# K10_reg_proto.net
KiCad netlist of a schematic drawn in EAGLE
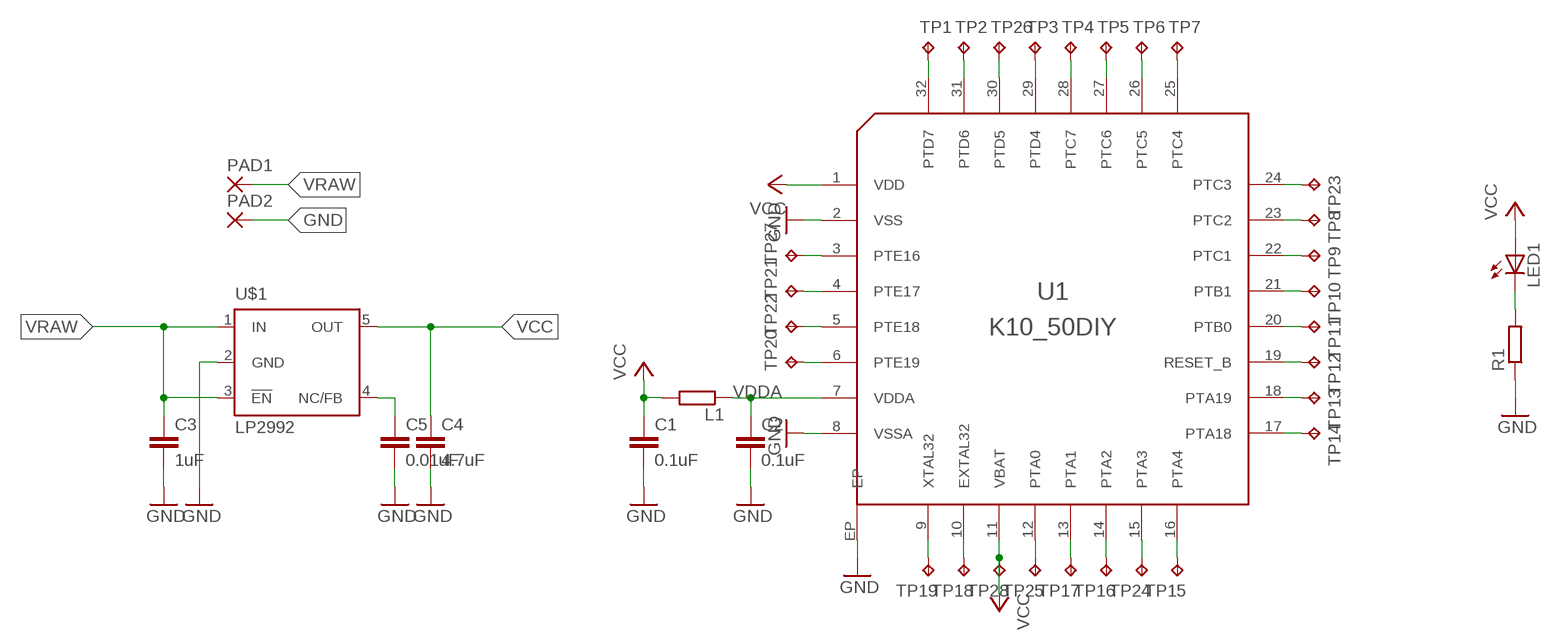
[diagram p0: schematic, sheet 1]

(export (version "E")
  (design (tool "Eeschema 10.0.6"))
  (components
    (comp (ref "C1")
      (value "0.1uF")
      (footprint "eagle-import:C0805")
      (libsource (lib "eagle-import") (part "C-EUC0805"))
    )
    (comp (ref "C2")
      (value "0.1uF")
      (footprint "eagle-import:C0805")
      (libsource (lib "eagle-import") (part "C-EUC0805"))
    )
    (comp (ref "C3")
      (value "1uF")
      (footprint "eagle-import:C0805")
      (libsource (lib "eagle-import") (part "C-EUC0805"))
    )
    (comp (ref "C4")
      (value "4.7uF")
      (footprint "eagle-import:C0805")
      (libsource (lib "eagle-import") (part "C-EUC0805"))
    )
    (comp (ref "C5")
      (value "0.01uF")
      (footprint "eagle-import:C0805")
      (libsource (lib "eagle-import") (part "C-EUC0805"))
    )
    (comp (ref "L1")
      (value "R-EU_R1206")
      (footprint "eagle-import:R1206")
      (libsource (lib "eagle-import") (part "R-EU_R1206"))
    )
    (comp (ref "LED1")
      (value "LEDSML0805")
      (footprint "eagle-import:SML0805")
      (libsource (lib "eagle-import") (part "LEDSML0805"))
    )
    (comp (ref "PAD1")
      (value "SMD2")
      (footprint "eagle-import:SMD1,27-2,54")
      (libsource (lib "eagle-import") (part "SMD2"))
    )
    (comp (ref "PAD2")
      (value "SMD2")
      (footprint "eagle-import:SMD1,27-2,54")
      (libsource (lib "eagle-import") (part "SMD2"))
    )
    (comp (ref "R1")
      (value "R-EU_R0805")
      (footprint "eagle-import:R0805")
      (libsource (lib "eagle-import") (part "R-EU_R0805"))
    )
    (comp (ref "TP1")
      (value "TPTP06R")
      (footprint "eagle-import:TP06R")
      (libsource (lib "eagle-import") (part "TPTP06R"))
    )
    (comp (ref "TP2")
      (value "TPTP06R")
      (footprint "eagle-import:TP06R")
      (libsource (lib "eagle-import") (part "TPTP06R"))
    )
    (comp (ref "TP3")
      (value "TPTP06R")
      (footprint "eagle-import:TP06R")
      (libsource (lib "eagle-import") (part "TPTP06R"))
    )
    (comp (ref "TP4")
      (value "TPTP06R")
      (footprint "eagle-import:TP06R")
      (libsource (lib "eagle-import") (part "TPTP06R"))
    )
    (comp (ref "TP5")
      (value "TPTP06R")
      (footprint "eagle-import:TP06R")
      (libsource (lib "eagle-import") (part "TPTP06R"))
    )
    (comp (ref "TP6")
      (value "TPTP06R")
      (footprint "eagle-import:TP06R")
      (libsource (lib "eagle-import") (part "TPTP06R"))
    )
    (comp (ref "TP7")
      (value "TPTP06R")
      (footprint "eagle-import:TP06R")
      (libsource (lib "eagle-import") (part "TPTP06R"))
    )
    (comp (ref "TP8")
      (value "TPTP06R")
      (footprint "eagle-import:TP06R")
      (libsource (lib "eagle-import") (part "TPTP06R"))
    )
    (comp (ref "TP9")
      (value "TPTP06R")
      (footprint "eagle-import:TP06R")
      (libsource (lib "eagle-import") (part "TPTP06R"))
    )
    (comp (ref "TP10")
      (value "TPTP06R")
      (footprint "eagle-import:TP06R")
      (libsource (lib "eagle-import") (part "TPTP06R"))
    )
    (comp (ref "TP11")
      (value "TPTP06R")
      (footprint "eagle-import:TP06R")
      (libsource (lib "eagle-import") (part "TPTP06R"))
    )
    (comp (ref "TP12")
      (value "TPTP06R")
      (footprint "eagle-import:TP06R")
      (libsource (lib "eagle-import") (part "TPTP06R"))
    )
    (comp (ref "TP13")
      (value "TPTP06R")
      (footprint "eagle-import:TP06R")
      (libsource (lib "eagle-import") (part "TPTP06R"))
    )
    (comp (ref "TP14")
      (value "TPTP06R")
      (footprint "eagle-import:TP06R")
      (libsource (lib "eagle-import") (part "TPTP06R"))
    )
    (comp (ref "TP15")
      (value "TPTP06R")
      (footprint "eagle-import:TP06R")
      (libsource (lib "eagle-import") (part "TPTP06R"))
    )
    (comp (ref "TP16")
      (value "TPTP06R")
      (footprint "eagle-import:TP06R")
      (libsource (lib "eagle-import") (part "TPTP06R"))
    )
    (comp (ref "TP17")
      (value "TPTP06R")
      (footprint "eagle-import:TP06R")
      (libsource (lib "eagle-import") (part "TPTP06R"))
    )
    (comp (ref "TP18")
      (value "TPTP06R")
      (footprint "eagle-import:TP06R")
      (libsource (lib "eagle-import") (part "TPTP06R"))
    )
    (comp (ref "TP19")
      (value "TPTP06R")
      (footprint "eagle-import:TP06R")
      (libsource (lib "eagle-import") (part "TPTP06R"))
    )
    (comp (ref "TP20")
      (value "TPTP06R")
      (footprint "eagle-import:TP06R")
      (libsource (lib "eagle-import") (part "TPTP06R"))
    )
    (comp (ref "TP21")
      (value "TPTP06R")
      (footprint "eagle-import:TP06R")
      (libsource (lib "eagle-import") (part "TPTP06R"))
    )
    (comp (ref "TP22")
      (value "TPTP06R")
      (footprint "eagle-import:TP06R")
      (libsource (lib "eagle-import") (part "TPTP06R"))
    )
    (comp (ref "TP23")
      (value "TPTP06R")
      (footprint "eagle-import:TP06R")
      (libsource (lib "eagle-import") (part "TPTP06R"))
    )
    (comp (ref "TP24")
      (value "TPTP06R")
      (footprint "eagle-import:TP06R")
      (libsource (lib "eagle-import") (part "TPTP06R"))
    )
    (comp (ref "TP25")
      (value "TPTP06R")
      (footprint "eagle-import:TP06R")
      (libsource (lib "eagle-import") (part "TPTP06R"))
    )
    (comp (ref "TP26")
      (value "TPTP06R")
      (footprint "eagle-import:TP06R")
      (libsource (lib "eagle-import") (part "TPTP06R"))
    )
    (comp (ref "TP27")
      (value "TPTP06R")
      (footprint "eagle-import:TP06R")
      (libsource (lib "eagle-import") (part "TPTP06R"))
    )
    (comp (ref "TP28")
      (value "TPTP06R")
      (footprint "eagle-import:TP06R")
      (libsource (lib "eagle-import") (part "TPTP06R"))
    )
    (comp (ref "U$1")
      (value "LP2992")
      (footprint "eagle-import:SOT-23DBV")
      (libsource (lib "eagle-import") (part "LP2992"))
    )
    (comp (ref "U1")
      (value "K10_50DIY")
      (footprint "eagle-import:QFN32-DIY")
      (libsource (lib "eagle-import") (part "K10_50DIY"))
    )
  )
  (nets
    (net (code "1") (name "/VDDA") (class "Default")
      (node (ref "C2") (pin "1") (pinfunction "1_1") (pintype "passive"))
      (node (ref "L1") (pin "1") (pinfunction "1_1") (pintype "passive"))
      (node (ref "U1") (pin "7") (pinfunction "VDDA_7") (pintype "bidirectional"))
    )
    (net (code "2") (name "GND") (class "Default")
      (node (ref "C1") (pin "2") (pinfunction "2_2") (pintype "passive"))
      (node (ref "C2") (pin "2") (pinfunction "2_2") (pintype "passive"))
      (node (ref "C3") (pin "2") (pinfunction "2_2") (pintype "passive"))
      (node (ref "C4") (pin "2") (pinfunction "2_2") (pintype "passive"))
      (node (ref "C5") (pin "2") (pinfunction "2_2") (pintype "passive"))
      (node (ref "PAD2") (pin "1") (pinfunction "P_1") (pintype "passive"))
      (node (ref "R1") (pin "1") (pinfunction "1_1") (pintype "passive"))
      (node (ref "U$1") (pin "2") (pinfunction "GND_2") (pintype "power_in"))
      (node (ref "U1") (pin "2") (pinfunction "VSS_2") (pintype "bidirectional"))
      (node (ref "U1") (pin "8") (pinfunction "VSSA_8") (pintype "bidirectional"))
      (node (ref "U1") (pin "EP") (pinfunction "EP_EP") (pintype "bidirectional"))
    )
    (net (code "3") (name "Net-(LED1-PadC)") (class "Default")
      (node (ref "LED1") (pin "C") (pinfunction "C_C") (pintype "passive"))
      (node (ref "R1") (pin "2") (pinfunction "2_2") (pintype "passive"))
    )
    (net (code "4") (name "Net-(U$1-NC{slash}FB)") (class "Default")
      (node (ref "C5") (pin "1") (pinfunction "1_1") (pintype "passive"))
      (node (ref "U$1") (pin "4") (pinfunction "NC/FB_4") (pintype "passive"))
    )
    (net (code "5") (name "Net-(U1-EXTAL32)") (class "Default")
      (node (ref "TP18") (pin "TP") (pinfunction "TP_TP") (pintype "input"))
      (node (ref "U1") (pin "10") (pinfunction "EXTAL32_10") (pintype "bidirectional"))
    )
    (net (code "6") (name "Net-(U1-PTA0)") (class "Default")
      (node (ref "TP25") (pin "TP") (pinfunction "TP_TP") (pintype "input"))
      (node (ref "U1") (pin "12") (pinfunction "PTA0_12") (pintype "bidirectional"))
    )
    (net (code "7") (name "Net-(U1-PTA1)") (class "Default")
      (node (ref "TP17") (pin "TP") (pinfunction "TP_TP") (pintype "input"))
      (node (ref "U1") (pin "13") (pinfunction "PTA1_13") (pintype "bidirectional"))
    )
    (net (code "8") (name "Net-(U1-PTA2)") (class "Default")
      (node (ref "TP16") (pin "TP") (pinfunction "TP_TP") (pintype "input"))
      (node (ref "U1") (pin "14") (pinfunction "PTA2_14") (pintype "bidirectional"))
    )
    (net (code "9") (name "Net-(U1-PTA3)") (class "Default")
      (node (ref "TP24") (pin "TP") (pinfunction "TP_TP") (pintype "input"))
      (node (ref "U1") (pin "15") (pinfunction "PTA3_15") (pintype "bidirectional"))
    )
    (net (code "10") (name "Net-(U1-PTA4)") (class "Default")
      (node (ref "TP15") (pin "TP") (pinfunction "TP_TP") (pintype "input"))
      (node (ref "U1") (pin "16") (pinfunction "PTA4_16") (pintype "bidirectional"))
    )
    (net (code "11") (name "Net-(U1-PTA18)") (class "Default")
      (node (ref "TP14") (pin "TP") (pinfunction "TP_TP") (pintype "input"))
      (node (ref "U1") (pin "17") (pinfunction "PTA18_17") (pintype "bidirectional"))
    )
    (net (code "12") (name "Net-(U1-PTA19)") (class "Default")
      (node (ref "TP13") (pin "TP") (pinfunction "TP_TP") (pintype "input"))
      (node (ref "U1") (pin "18") (pinfunction "PTA19_18") (pintype "bidirectional"))
    )
    (net (code "13") (name "Net-(U1-PTB0)") (class "Default")
      (node (ref "TP11") (pin "TP") (pinfunction "TP_TP") (pintype "input"))
      (node (ref "U1") (pin "20") (pinfunction "PTB0_20") (pintype "bidirectional"))
    )
    (net (code "14") (name "Net-(U1-PTB1)") (class "Default")
      (node (ref "TP10") (pin "TP") (pinfunction "TP_TP") (pintype "input"))
      (node (ref "U1") (pin "21") (pinfunction "PTB1_21") (pintype "bidirectional"))
    )
    (net (code "15") (name "Net-(U1-PTC1)") (class "Default")
      (node (ref "TP9") (pin "TP") (pinfunction "TP_TP") (pintype "input"))
      (node (ref "U1") (pin "22") (pinfunction "PTC1_22") (pintype "bidirectional"))
    )
    (net (code "16") (name "Net-(U1-PTC2)") (class "Default")
      (node (ref "TP8") (pin "TP") (pinfunction "TP_TP") (pintype "input"))
      (node (ref "U1") (pin "23") (pinfunction "PTC2_23") (pintype "bidirectional"))
    )
    (net (code "17") (name "Net-(U1-PTC3)") (class "Default")
      (node (ref "TP23") (pin "TP") (pinfunction "TP_TP") (pintype "input"))
      (node (ref "U1") (pin "24") (pinfunction "PTC3_24") (pintype "bidirectional"))
    )
    (net (code "18") (name "Net-(U1-PTC4)") (class "Default")
      (node (ref "TP7") (pin "TP") (pinfunction "TP_TP") (pintype "input"))
      (node (ref "U1") (pin "25") (pinfunction "PTC4_25") (pintype "bidirectional"))
    )
    (net (code "19") (name "Net-(U1-PTC5)") (class "Default")
      (node (ref "TP6") (pin "TP") (pinfunction "TP_TP") (pintype "input"))
      (node (ref "U1") (pin "26") (pinfunction "PTC5_26") (pintype "bidirectional"))
    )
    (net (code "20") (name "Net-(U1-PTC6)") (class "Default")
      (node (ref "TP5") (pin "TP") (pinfunction "TP_TP") (pintype "input"))
      (node (ref "U1") (pin "27") (pinfunction "PTC6_27") (pintype "bidirectional"))
    )
    (net (code "21") (name "Net-(U1-PTC7)") (class "Default")
      (node (ref "TP4") (pin "TP") (pinfunction "TP_TP") (pintype "input"))
      (node (ref "U1") (pin "28") (pinfunction "PTC7_28") (pintype "bidirectional"))
    )
    (net (code "22") (name "Net-(U1-PTD4)") (class "Default")
      (node (ref "TP3") (pin "TP") (pinfunction "TP_TP") (pintype "input"))
      (node (ref "U1") (pin "29") (pinfunction "PTD4_29") (pintype "bidirectional"))
    )
    (net (code "23") (name "Net-(U1-PTD5)") (class "Default")
      (node (ref "TP26") (pin "TP") (pinfunction "TP_TP") (pintype "input"))
      (node (ref "U1") (pin "30") (pinfunction "PTD5_30") (pintype "bidirectional"))
    )
    (net (code "24") (name "Net-(U1-PTD6)") (class "Default")
      (node (ref "TP2") (pin "TP") (pinfunction "TP_TP") (pintype "input"))
      (node (ref "U1") (pin "31") (pinfunction "PTD6_31") (pintype "bidirectional"))
    )
    (net (code "25") (name "Net-(U1-PTD7)") (class "Default")
      (node (ref "TP1") (pin "TP") (pinfunction "TP_TP") (pintype "input"))
      (node (ref "U1") (pin "32") (pinfunction "PTD7_32") (pintype "bidirectional"))
    )
    (net (code "26") (name "Net-(U1-PTE16)") (class "Default")
      (node (ref "TP27") (pin "TP") (pinfunction "TP_TP") (pintype "input"))
      (node (ref "U1") (pin "3") (pinfunction "PTE16_3") (pintype "bidirectional"))
    )
    (net (code "27") (name "Net-(U1-PTE17)") (class "Default")
      (node (ref "TP21") (pin "TP") (pinfunction "TP_TP") (pintype "input"))
      (node (ref "U1") (pin "4") (pinfunction "PTE17_4") (pintype "bidirectional"))
    )
    (net (code "28") (name "Net-(U1-PTE18)") (class "Default")
      (node (ref "TP22") (pin "TP") (pinfunction "TP_TP") (pintype "input"))
      (node (ref "U1") (pin "5") (pinfunction "PTE18_5") (pintype "bidirectional"))
    )
    (net (code "29") (name "Net-(U1-PTE19)") (class "Default")
      (node (ref "TP20") (pin "TP") (pinfunction "TP_TP") (pintype "input"))
      (node (ref "U1") (pin "6") (pinfunction "PTE19_6") (pintype "bidirectional"))
    )
    (net (code "30") (name "Net-(U1-RESET_B)") (class "Default")
      (node (ref "TP12") (pin "TP") (pinfunction "TP_TP") (pintype "input"))
      (node (ref "U1") (pin "19") (pinfunction "RESET_B_19") (pintype "bidirectional"))
    )
    (net (code "31") (name "Net-(U1-XTAL32)") (class "Default")
      (node (ref "TP19") (pin "TP") (pinfunction "TP_TP") (pintype "input"))
      (node (ref "U1") (pin "9") (pinfunction "XTAL32_9") (pintype "bidirectional"))
    )
    (net (code "32") (name "VCC") (class "Default")
      (node (ref "C1") (pin "1") (pinfunction "1_1") (pintype "passive"))
      (node (ref "C4") (pin "1") (pinfunction "1_1") (pintype "passive"))
      (node (ref "L1") (pin "2") (pinfunction "2_2") (pintype "passive"))
      (node (ref "LED1") (pin "A") (pinfunction "A_A") (pintype "passive"))
      (node (ref "TP28") (pin "TP") (pinfunction "TP_TP") (pintype "input"))
      (node (ref "U$1") (pin "5") (pinfunction "OUT_5") (pintype "passive"))
      (node (ref "U1") (pin "1") (pinfunction "VDD_1") (pintype "bidirectional"))
      (node (ref "U1") (pin "11") (pinfunction "VBAT_11") (pintype "bidirectional"))
    )
    (net (code "33") (name "VRAW") (class "Default")
      (node (ref "C3") (pin "1") (pinfunction "1_1") (pintype "passive"))
      (node (ref "PAD1") (pin "1") (pinfunction "P_1") (pintype "passive"))
      (node (ref "U$1") (pin "1") (pinfunction "IN_1") (pintype "input"))
      (node (ref "U$1") (pin "3") (pinfunction "~{EN}_3") (pintype "input"))
    )
  )
)
